# v2_power_board.net
KiCad netlist of a schematic drawn in EAGLE
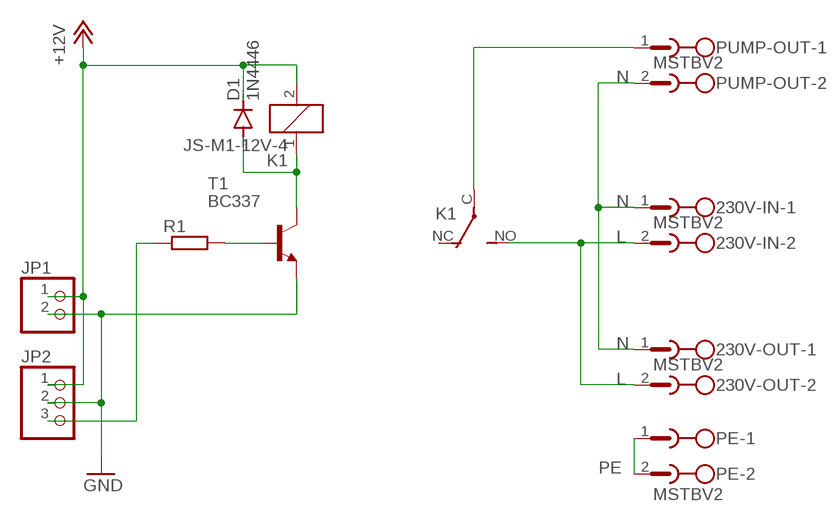
[diagram p0: schematic, sheet 1]

(export (version "E")
  (design (tool "Eeschema 10.0.6"))
  (components
    (comp (ref "230V-IN")
      (value "MSTBV2")
      (footprint "eagle-import:MSTBV2")
      (fields (field (name "MPN") "MSTBV 2,5/2-GF-5.08"))
      (libsource (lib "eagle-import") (part "MSTBV2"))
    )
    (comp (ref "230V-OUT")
      (value "MSTBV2")
      (footprint "eagle-import:MSTBV2")
      (fields (field (name "MPN") "MSTBV 2,5/2-GF-5.08"))
      (libsource (lib "eagle-import") (part "MSTBV2"))
    )
    (comp (ref "D1")
      (value "1N4446")
      (footprint "eagle-import:DO35-10")
      (libsource (lib "eagle-import") (part "1N4446"))
    )
    (comp (ref "JP1")
      (value "PINHD-1X2")
      (footprint "eagle-import:1X02")
      (libsource (lib "eagle-import") (part "PINHD-1X2"))
    )
    (comp (ref "JP2")
      (value "PINHD-1X3")
      (footprint "eagle-import:1X03")
      (libsource (lib "eagle-import") (part "PINHD-1X3"))
    )
    (comp (ref "K1")
      (value "JS-M1-12V-4")
      (footprint "eagle-import:JS-M")
      (fields (field (name "MPN") "JSM1-12V-4"))
      (libsource (lib "eagle-import") (part "JS-M1-12V-4"))
    )
    (comp (ref "PE")
      (value "MSTBV2")
      (footprint "eagle-import:MSTBV2")
      (fields (field (name "MPN") "MSTBV 2,5/2-GF-5.08"))
      (libsource (lib "eagle-import") (part "MSTBV2"))
    )
    (comp (ref "PUMP-OUT")
      (value "MSTBV2")
      (footprint "eagle-import:MSTBV2")
      (fields (field (name "MPN") "MSTBV 2,5/2-GF-5.08"))
      (libsource (lib "eagle-import") (part "MSTBV2"))
    )
    (comp (ref "R1")
      (value "R-EU_R1206")
      (footprint "eagle-import:R1206")
      (libsource (lib "eagle-import") (part "R-EU_R1206"))
    )
    (comp (ref "T1")
      (value "BC337")
      (footprint "eagle-import:TO92")
      (libsource (lib "eagle-import") (part "BC337"))
    )
  )
  (nets
    (net (code "1") (name "+12V") (class "Default")
      (node (ref "D1") (pin "C") (pinfunction "C_C") (pintype "passive"))
      (node (ref "JP1") (pin "1") (pinfunction "1_1") (pintype "passive"))
      (node (ref "JP2") (pin "1") (pinfunction "1_1") (pintype "passive"))
      (node (ref "K1") (pin "2") (pinfunction "2_2") (pintype "passive"))
    )
    (net (code "2") (name "/L") (class "Default")
      (node (ref "230V-IN") (pin "2") (pinfunction "1_2") (pintype "passive"))
      (node (ref "230V-OUT") (pin "2") (pinfunction "1_2") (pintype "passive"))
      (node (ref "K1") (pin "NO") (pinfunction "S_NO") (pintype "passive"))
    )
    (net (code "3") (name "/N") (class "Default")
      (node (ref "230V-IN") (pin "1") (pinfunction "1_1") (pintype "passive"))
      (node (ref "230V-OUT") (pin "1") (pinfunction "1_1") (pintype "passive"))
      (node (ref "PUMP-OUT") (pin "2") (pinfunction "1_2") (pintype "passive"))
    )
    (net (code "4") (name "/PE") (class "Default")
      (node (ref "PE") (pin "1") (pinfunction "1_1") (pintype "passive"))
      (node (ref "PE") (pin "2") (pinfunction "1_2") (pintype "passive"))
    )
    (net (code "5") (name "GND") (class "Default")
      (node (ref "JP1") (pin "2") (pinfunction "2_2") (pintype "passive"))
      (node (ref "JP2") (pin "2") (pinfunction "2_2") (pintype "passive"))
      (node (ref "T1") (pin "1") (pinfunction "E_1") (pintype "passive"))
    )
    (net (code "6") (name "Net-(JP2-Pad3)") (class "Default")
      (node (ref "JP2") (pin "3") (pinfunction "3_3") (pintype "passive"))
      (node (ref "R1") (pin "1") (pinfunction "1_1") (pintype "passive"))
    )
    (net (code "7") (name "Net-(K1B-P)") (class "Default")
      (node (ref "K1") (pin "C") (pinfunction "P_C") (pintype "passive"))
      (node (ref "PUMP-OUT") (pin "1") (pinfunction "1_1") (pintype "passive"))
    )
    (net (code "8") (name "Net-(T1-B)") (class "Default")
      (node (ref "R1") (pin "2") (pinfunction "2_2") (pintype "passive"))
      (node (ref "T1") (pin "2") (pinfunction "B_2") (pintype "passive"))
    )
    (net (code "9") (name "Net-(T1-C)") (class "Default")
      (node (ref "D1") (pin "A") (pinfunction "A_A") (pintype "passive"))
      (node (ref "K1") (pin "1") (pinfunction "1_1") (pintype "passive"))
      (node (ref "T1") (pin "3") (pinfunction "C_3") (pintype "passive"))
    )
    (net (code "10") (name "unconnected-(K1B-O-PadNC)") (class "Default")
      (node (ref "K1") (pin "NC") (pinfunction "O_NC") (pintype "passive"))
    )
  )
)
